# Shield_Cutter-V1.net
KiCad netlist of a schematic drawn in EAGLE
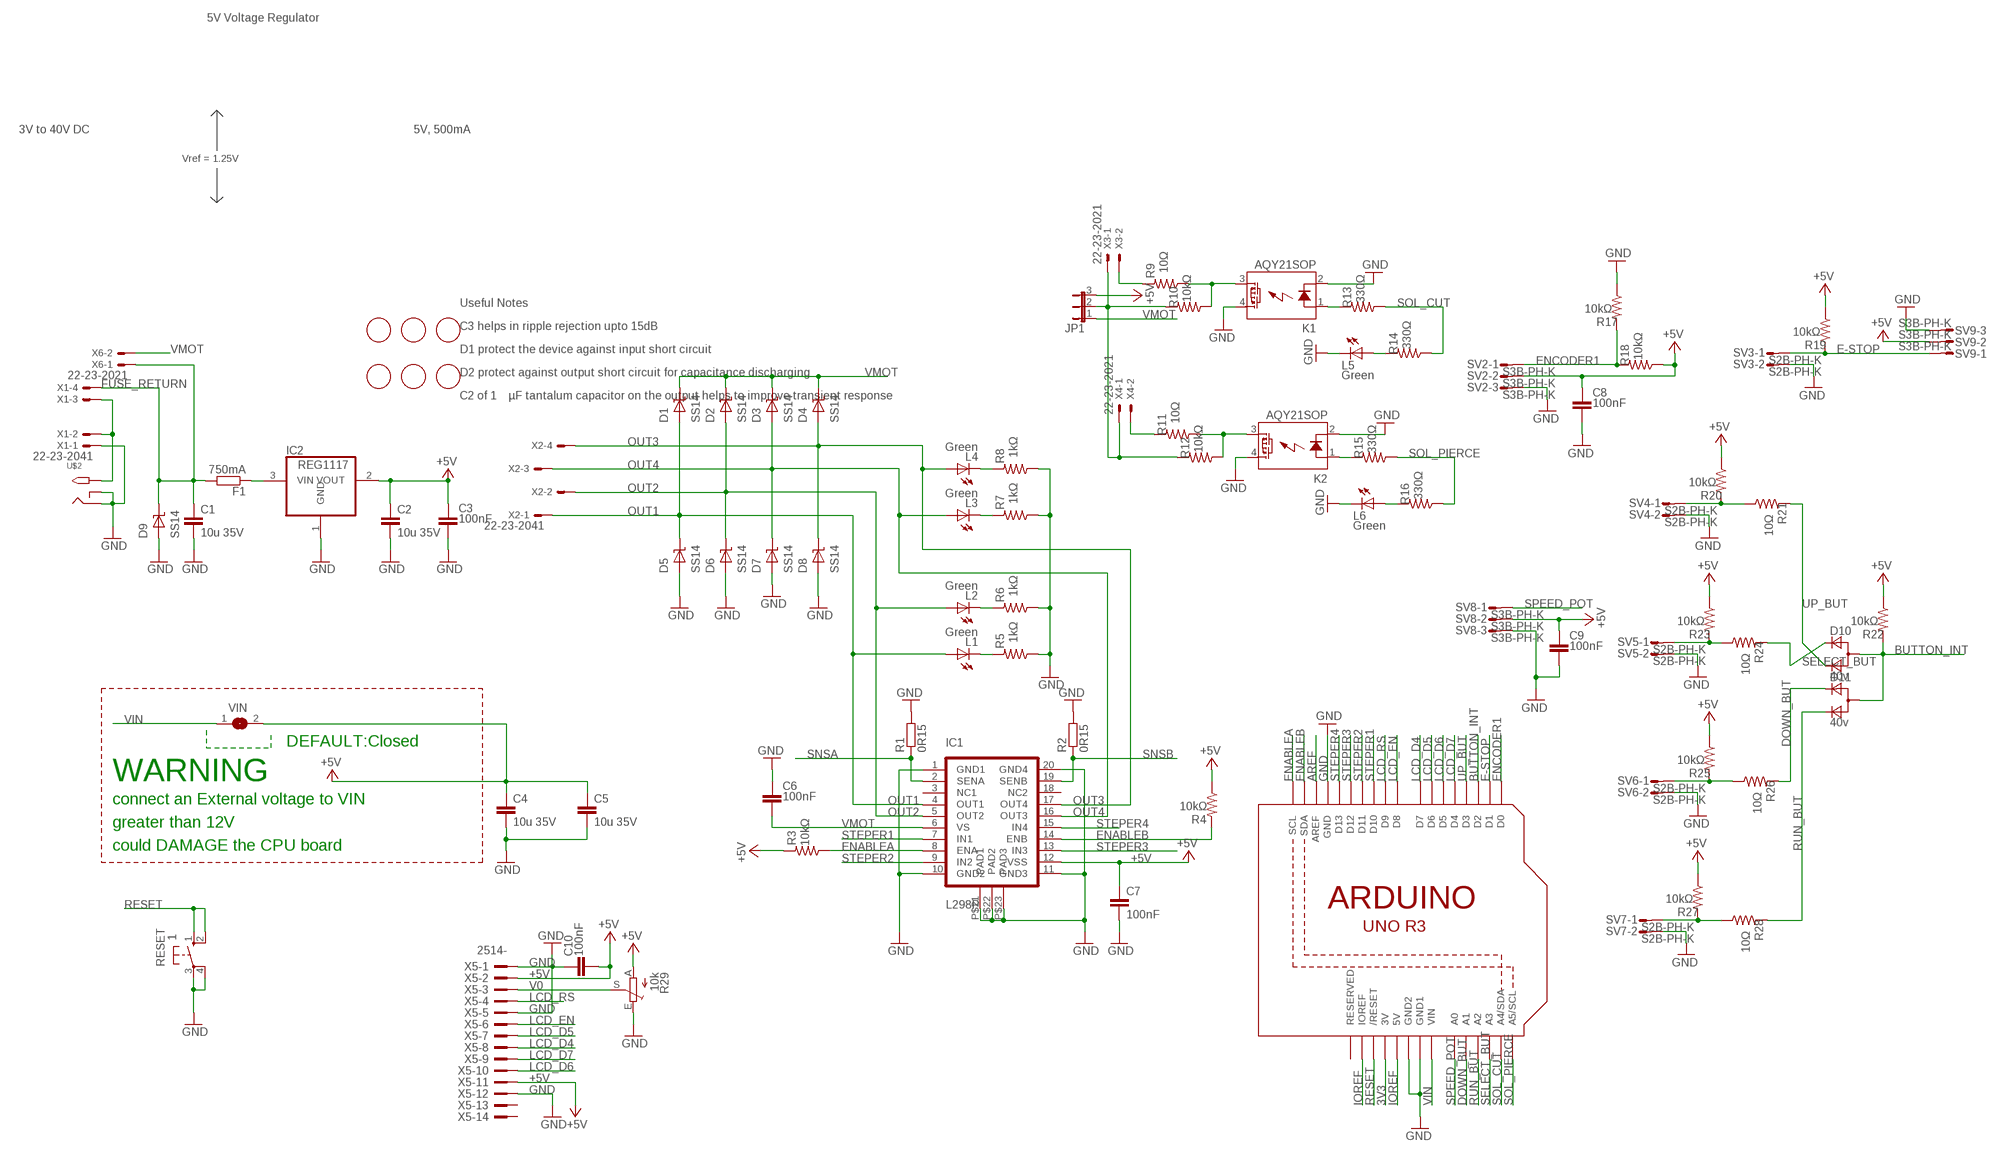
[diagram p0: schematic, sheet 1]

(export (version "E")
  (design (tool "Eeschema 10.0.6"))
  (components
    (comp (ref "C1")
      (value "10u 35V")
      (footprint "eagle-import:C1210")
      (libsource (lib "eagle-import") (part "C-EUC1210"))
    )
    (comp (ref "C2")
      (value "10u 35V")
      (footprint "eagle-import:C1210")
      (libsource (lib "eagle-import") (part "C-EUC1210"))
    )
    (comp (ref "C3")
      (value "100nF")
      (footprint "eagle-import:C0805")
      (libsource (lib "eagle-import") (part "rcl_C-EUC0805"))
    )
    (comp (ref "C4")
      (value "10u 35V")
      (footprint "eagle-import:C1210")
      (libsource (lib "eagle-import") (part "C-EUC1210"))
    )
    (comp (ref "C5")
      (value "10u 35V")
      (footprint "eagle-import:C1210")
      (libsource (lib "eagle-import") (part "C-EUC1210"))
    )
    (comp (ref "C6")
      (value "100nF")
      (footprint "eagle-import:C0805")
      (libsource (lib "eagle-import") (part "rcl_C-EUC0805"))
    )
    (comp (ref "C7")
      (value "100nF")
      (footprint "eagle-import:C0805")
      (libsource (lib "eagle-import") (part "C-EUC0805"))
    )
    (comp (ref "C8")
      (value "100nF")
      (footprint "eagle-import:C0805")
      (libsource (lib "eagle-import") (part "rcl_C-EUC0805"))
    )
    (comp (ref "C9")
      (value "100nF")
      (footprint "eagle-import:C0805")
      (libsource (lib "eagle-import") (part "rcl_C-EUC0805"))
    )
    (comp (ref "C10")
      (value "100nF")
      (footprint "eagle-import:C0805")
      (libsource (lib "eagle-import") (part "rcl_C-EUC0805"))
    )
    (comp (ref "D1")
      (value "SS14")
      (footprint "eagle-import:SMA")
      (libsource (lib "eagle-import") (part "SS14"))
    )
    (comp (ref "D2")
      (value "SS14")
      (footprint "eagle-import:SMA")
      (libsource (lib "eagle-import") (part "SS14"))
    )
    (comp (ref "D3")
      (value "SS14")
      (footprint "eagle-import:SMA")
      (libsource (lib "eagle-import") (part "SS14"))
    )
    (comp (ref "D4")
      (value "SS14")
      (footprint "eagle-import:SMA")
      (libsource (lib "eagle-import") (part "SS14"))
    )
    (comp (ref "D5")
      (value "SS14")
      (footprint "eagle-import:SMA")
      (libsource (lib "eagle-import") (part "SS14"))
    )
    (comp (ref "D6")
      (value "SS14")
      (footprint "eagle-import:SMA")
      (libsource (lib "eagle-import") (part "SS14"))
    )
    (comp (ref "D7")
      (value "SS14")
      (footprint "eagle-import:SMA")
      (libsource (lib "eagle-import") (part "SS14"))
    )
    (comp (ref "D8")
      (value "SS14")
      (footprint "eagle-import:SMA")
      (libsource (lib "eagle-import") (part "SS14"))
    )
    (comp (ref "D9")
      (value "SS14")
      (footprint "eagle-import:SMA")
      (libsource (lib "eagle-import") (part "SS14"))
    )
    (comp (ref "D10")
      (value "40v")
      (footprint "eagle-import:SOT323")
      (libsource (lib "eagle-import") (part "D_2CSOT323"))
    )
    (comp (ref "D11")
      (value "40v")
      (footprint "eagle-import:SOT323")
      (libsource (lib "eagle-import") (part "D_2CSOT323"))
    )
    (comp (ref "F1")
      (value "750mA")
      (footprint "eagle-import:R1206")
      (libsource (lib "eagle-import") (part "R-EU_R1206"))
    )
    (comp (ref "FID1")
      (value "FIDUCIALMOUNT")
      (footprint "eagle-import:FIDUCIA-MOUNT")
      (libsource (lib "eagle-import") (part "FIDUCIALMOUNT"))
    )
    (comp (ref "FID2")
      (value "FIDUCIALMOUNT")
      (footprint "eagle-import:FIDUCIA-MOUNT")
      (libsource (lib "eagle-import") (part "FIDUCIALMOUNT"))
    )
    (comp (ref "FID3")
      (value "FIDUCIALMOUNT")
      (footprint "eagle-import:FIDUCIA-MOUNT")
      (libsource (lib "eagle-import") (part "FIDUCIALMOUNT"))
    )
    (comp (ref "FID4")
      (value "FIDUCIALMOUNT")
      (footprint "eagle-import:FIDUCIA-MOUNT")
      (libsource (lib "eagle-import") (part "FIDUCIALMOUNT"))
    )
    (comp (ref "FID5")
      (value "FIDUCIALMOUNT")
      (footprint "eagle-import:FIDUCIA-MOUNT")
      (libsource (lib "eagle-import") (part "FIDUCIALMOUNT"))
    )
    (comp (ref "FID6")
      (value "FIDUCIALMOUNT")
      (footprint "eagle-import:FIDUCIA-MOUNT")
      (libsource (lib "eagle-import") (part "FIDUCIALMOUNT"))
    )
    (comp (ref "IC1")
      (value "L298P")
      (footprint "eagle-import:POWER-SO20")
      (libsource (lib "eagle-import") (part "L298P"))
    )
    (comp (ref "IC2")
      (value "REG1117")
      (footprint "eagle-import:SOT223")
      (libsource (lib "eagle-import") (part "REG1117"))
    )
    (comp (ref "JP1")
      (value "JP2E")
      (footprint "eagle-import:JP2")
      (libsource (lib "eagle-import") (part "JP2E"))
    )
    (comp (ref "K1")
      (value "AQY21SOP")
      (footprint "eagle-import:SOP04")
      (libsource (lib "eagle-import") (part "AQYSOP21"))
    )
    (comp (ref "K2")
      (value "AQY21SOP")
      (footprint "eagle-import:SOP04")
      (libsource (lib "eagle-import") (part "AQYSOP21"))
    )
    (comp (ref "L1")
      (value "Green")
      (footprint "eagle-import:CHIPLED_0805")
      (libsource (lib "eagle-import") (part "LEDCHIPLED_0805"))
    )
    (comp (ref "L2")
      (value "Green")
      (footprint "eagle-import:CHIPLED_0805")
      (libsource (lib "eagle-import") (part "LEDCHIPLED_0805"))
    )
    (comp (ref "L3")
      (value "Green")
      (footprint "eagle-import:CHIPLED_0805")
      (libsource (lib "eagle-import") (part "LEDCHIPLED_0805"))
    )
    (comp (ref "L4")
      (value "Green")
      (footprint "eagle-import:CHIPLED_0805")
      (libsource (lib "eagle-import") (part "LEDCHIPLED_0805"))
    )
    (comp (ref "L5")
      (value "Green")
      (footprint "eagle-import:CHIPLED_0805")
      (libsource (lib "eagle-import") (part "LEDCHIPLED_0805"))
    )
    (comp (ref "L6")
      (value "Green")
      (footprint "eagle-import:CHIPLED_0805")
      (libsource (lib "eagle-import") (part "LEDCHIPLED_0805"))
    )
    (comp (ref "R1")
      (value "0R15")
      (footprint "eagle-import:R1206")
      (libsource (lib "eagle-import") (part "R-EU_R1206"))
    )
    (comp (ref "R2")
      (value "0R15")
      (footprint "eagle-import:R1206")
      (libsource (lib "eagle-import") (part "R-EU_R1206"))
    )
    (comp (ref "R3")
      (value "10kΩ")
      (footprint "eagle-import:R0805")
      (libsource (lib "eagle-import") (part "R-US_R0805"))
    )
    (comp (ref "R4")
      (value "10kΩ")
      (footprint "eagle-import:R0805")
      (libsource (lib "eagle-import") (part "R-US_R0805"))
    )
    (comp (ref "R5")
      (value "1kΩ")
      (footprint "eagle-import:R0805")
      (libsource (lib "eagle-import") (part "R-US_R0805"))
    )
    (comp (ref "R6")
      (value "1kΩ")
      (footprint "eagle-import:R0805")
      (libsource (lib "eagle-import") (part "R-US_R0805"))
    )
    (comp (ref "R7")
      (value "1kΩ")
      (footprint "eagle-import:R0805")
      (libsource (lib "eagle-import") (part "R-US_R0805"))
    )
    (comp (ref "R8")
      (value "1kΩ")
      (footprint "eagle-import:R0805")
      (libsource (lib "eagle-import") (part "R-US_R0805"))
    )
    (comp (ref "R9")
      (value "10Ω")
      (footprint "eagle-import:R0805")
      (libsource (lib "eagle-import") (part "R-US_R0805"))
    )
    (comp (ref "R10")
      (value "10kΩ")
      (footprint "eagle-import:R0805")
      (libsource (lib "eagle-import") (part "R-US_R0805"))
    )
    (comp (ref "R11")
      (value "10Ω")
      (footprint "eagle-import:R0805")
      (libsource (lib "eagle-import") (part "R-US_R0805"))
    )
    (comp (ref "R12")
      (value "10kΩ")
      (footprint "eagle-import:R0805")
      (libsource (lib "eagle-import") (part "R-US_R0805"))
    )
    (comp (ref "R13")
      (value "330Ω")
      (footprint "eagle-import:R0805")
      (libsource (lib "eagle-import") (part "R-US_R0805"))
    )
    (comp (ref "R14")
      (value "330Ω")
      (footprint "eagle-import:R0805")
      (libsource (lib "eagle-import") (part "R-US_R0805"))
    )
    (comp (ref "R15")
      (value "330Ω")
      (footprint "eagle-import:R0805")
      (libsource (lib "eagle-import") (part "R-US_R0805"))
    )
    (comp (ref "R16")
      (value "330Ω")
      (footprint "eagle-import:R0805")
      (libsource (lib "eagle-import") (part "R-US_R0805"))
    )
    (comp (ref "R17")
      (value "10kΩ")
      (footprint "eagle-import:R0805")
      (libsource (lib "eagle-import") (part "R-US_R0805"))
    )
    (comp (ref "R18")
      (value "10kΩ")
      (footprint "eagle-import:R0805")
      (libsource (lib "eagle-import") (part "R-US_R0805"))
    )
    (comp (ref "R19")
      (value "10kΩ")
      (footprint "eagle-import:R0805")
      (libsource (lib "eagle-import") (part "R-US_R0805"))
    )
    (comp (ref "R20")
      (value "10kΩ")
      (footprint "eagle-import:R0805")
      (libsource (lib "eagle-import") (part "R-US_R0805"))
    )
    (comp (ref "R21")
      (value "10Ω")
      (footprint "eagle-import:R0805")
      (libsource (lib "eagle-import") (part "R-US_R0805"))
    )
    (comp (ref "R22")
      (value "10kΩ")
      (footprint "eagle-import:M0805")
      (libsource (lib "eagle-import") (part "R-US_M0805"))
    )
    (comp (ref "R23")
      (value "10kΩ")
      (footprint "eagle-import:R0805")
      (libsource (lib "eagle-import") (part "R-US_R0805"))
    )
    (comp (ref "R24")
      (value "10Ω")
      (footprint "eagle-import:R0805")
      (libsource (lib "eagle-import") (part "R-US_R0805"))
    )
    (comp (ref "R25")
      (value "10kΩ")
      (footprint "eagle-import:R0805")
      (libsource (lib "eagle-import") (part "R-US_R0805"))
    )
    (comp (ref "R26")
      (value "10Ω")
      (footprint "eagle-import:R0805")
      (libsource (lib "eagle-import") (part "R-US_R0805"))
    )
    (comp (ref "R27")
      (value "10kΩ")
      (footprint "eagle-import:R0805")
      (libsource (lib "eagle-import") (part "R-US_R0805"))
    )
    (comp (ref "R28")
      (value "10Ω")
      (footprint "eagle-import:R0805")
      (libsource (lib "eagle-import") (part "R-US_R0805"))
    )
    (comp (ref "R29")
      (value "10k")
      (footprint "eagle-import:S64W")
      (libsource (lib "eagle-import") (part "TRIM_EU-S64W"))
    )
    (comp (ref "RESET")
      (value "1")
      (footprint "eagle-import:B3F-10XX")
      (fields (field (name "MPN") "B3F-1000"))
      (libsource (lib "eagle-import") (part "10-XX"))
    )
    (comp (ref "SV2")
      (value "S3B-PH-K")
      (footprint "eagle-import:S03P")
      (libsource (lib "eagle-import") (part "S03P"))
    )
    (comp (ref "SV3")
      (value "S2B-PH-K")
      (footprint "eagle-import:S02P")
      (libsource (lib "eagle-import") (part "S02P"))
    )
    (comp (ref "SV4")
      (value "S2B-PH-K")
      (footprint "eagle-import:S02P")
      (libsource (lib "eagle-import") (part "S02P"))
    )
    (comp (ref "SV5")
      (value "S2B-PH-K")
      (footprint "eagle-import:S02P")
      (libsource (lib "eagle-import") (part "S02P"))
    )
    (comp (ref "SV6")
      (value "S2B-PH-K")
      (footprint "eagle-import:S02P")
      (libsource (lib "eagle-import") (part "S02P"))
    )
    (comp (ref "SV7")
      (value "S2B-PH-K")
      (footprint "eagle-import:S02P")
      (libsource (lib "eagle-import") (part "S02P"))
    )
    (comp (ref "SV8")
      (value "S3B-PH-K")
      (footprint "eagle-import:S03P")
      (libsource (lib "eagle-import") (part "S03P"))
    )
    (comp (ref "SV9")
      (value "S3B-PH-K")
      (footprint "eagle-import:S03P")
      (libsource (lib "eagle-import") (part "S03P"))
    )
    (comp (ref "U$2")
      (value "2.1MMJACKTHM")
      (footprint "eagle-import:PJ-102A")
      (libsource (lib "eagle-import") (part "2.1MMJACKTHM"))
    )
    (comp (ref "U1")
      (value "ARDUINOR3-DIMENSION")
      (footprint "eagle-import:ARDUINOR3")
      (libsource (lib "eagle-import") (part "ARDUINOR3-DIMENSION"))
    )
    (comp (ref "VIN")
      (value "SJW")
      (footprint "eagle-import:SJW")
      (libsource (lib "eagle-import") (part "SJW"))
    )
    (comp (ref "X1")
      (value "22-23-2041")
      (footprint "eagle-import:22-23-2041")
      (fields (field (name "MF") "MOLEX"))
      (libsource (lib "eagle-import") (part "22-23-2041"))
    )
    (comp (ref "X2")
      (value "22-23-2041")
      (footprint "eagle-import:22-23-2041")
      (fields (field (name "MF") "MOLEX"))
      (libsource (lib "eagle-import") (part "22-23-2041"))
    )
    (comp (ref "X3")
      (value "22-23-2021")
      (footprint "eagle-import:22-23-2021")
      (fields (field (name "MF") "MOLEX"))
      (libsource (lib "eagle-import") (part "22-23-2021"))
    )
    (comp (ref "X4")
      (value "22-23-2021")
      (footprint "eagle-import:22-23-2021")
      (fields (field (name "MF") "MOLEX"))
      (libsource (lib "eagle-import") (part "22-23-2021"))
    )
    (comp (ref "X5")
      (value "2514-")
      (footprint "eagle-import:PAK100_2500-14")
      (libsource (lib "eagle-import") (part "2514-"))
    )
    (comp (ref "X6")
      (value "22-23-2021")
      (footprint "eagle-import:22-23-2021")
      (fields (field (name "MF") "MOLEX"))
      (libsource (lib "eagle-import") (part "22-23-2021"))
    )
  )
  (nets
    (net (code "1") (name "+5V") (class "Default")
      (node (ref "C10") (pin "2") (pinfunction "2_2") (pintype "passive"))
      (node (ref "C2") (pin "1") (pinfunction "1_1") (pintype "passive"))
      (node (ref "C3") (pin "1") (pinfunction "1_1") (pintype "passive"))
      (node (ref "C4") (pin "1") (pinfunction "1_1") (pintype "passive"))
      (node (ref "C5") (pin "1") (pinfunction "1_1") (pintype "passive"))
      (node (ref "C7") (pin "1") (pinfunction "1_1") (pintype "passive"))
      (node (ref "C8") (pin "1") (pinfunction "1_1") (pintype "passive"))
      (node (ref "C9") (pin "1") (pinfunction "1_1") (pintype "passive"))
      (node (ref "IC1") (pin "P$12") (pinfunction "VSS_P$12") (pintype "power_in"))
      (node (ref "IC2") (pin "2") (pinfunction "VOUT_2") (pintype "output"))
      (node (ref "JP1") (pin "3") (pinfunction "3_3") (pintype "passive"))
      (node (ref "R18") (pin "1") (pinfunction "1_1") (pintype "passive"))
      (node (ref "R19") (pin "1") (pinfunction "1_1") (pintype "passive"))
      (node (ref "R20") (pin "1") (pinfunction "1_1") (pintype "passive"))
      (node (ref "R22") (pin "1") (pinfunction "1_1") (pintype "passive"))
      (node (ref "R23") (pin "1") (pinfunction "1_1") (pintype "passive"))
      (node (ref "R25") (pin "1") (pinfunction "1_1") (pintype "passive"))
      (node (ref "R27") (pin "1") (pinfunction "1_1") (pintype "passive"))
      (node (ref "R29") (pin "A") (pinfunction "A_A") (pintype "passive"))
      (node (ref "R3") (pin "2") (pinfunction "2_2") (pintype "passive"))
      (node (ref "R4") (pin "1") (pinfunction "1_1") (pintype "passive"))
      (node (ref "SV2") (pin "2") (pinfunction "S_2") (pintype "passive"))
      (node (ref "SV8") (pin "2") (pinfunction "S_2") (pintype "passive"))
      (node (ref "SV9") (pin "2") (pinfunction "S_2") (pintype "passive"))
      (node (ref "VIN") (pin "2") (pinfunction "2_2") (pintype "passive"))
      (node (ref "X5") (pin "11") (pinfunction "KL_11") (pintype "passive"))
      (node (ref "X5") (pin "2") (pinfunction "KL_2") (pintype "passive"))
    )
    (net (code "2") (name "/3V3") (class "Default")
      (node (ref "U1") (pin "3V") (pinfunction "3V_3V") (pintype "power_in"))
    )
    (net (code "3") (name "/AREF") (class "Default")
      (node (ref "U1") (pin "AREF") (pinfunction "AREF_AREF") (pintype "bidirectional"))
    )
    (net (code "4") (name "/BUTTON_INT") (class "Default")
      (node (ref "D10") (pin "1") (pinfunction "A_1") (pintype "passive"))
      (node (ref "D11") (pin "1") (pinfunction "A_1") (pintype "passive"))
      (node (ref "R22") (pin "2") (pinfunction "2_2") (pintype "passive"))
      (node (ref "U1") (pin "D2") (pinfunction "D2_D2") (pintype "bidirectional"))
    )
    (net (code "5") (name "/DOWN_BUT") (class "Default")
      (node (ref "D11") (pin "2") (pinfunction "C1_2") (pintype "passive"))
      (node (ref "R26") (pin "2") (pinfunction "2_2") (pintype "passive"))
      (node (ref "U1") (pin "A1") (pinfunction "A1_A1") (pintype "bidirectional"))
    )
    (net (code "6") (name "/E-STOP") (class "Default")
      (node (ref "R19") (pin "2") (pinfunction "2_2") (pintype "passive"))
      (node (ref "SV3") (pin "1") (pinfunction "S_1") (pintype "passive"))
      (node (ref "SV9") (pin "1") (pinfunction "S_1") (pintype "passive"))
      (node (ref "U1") (pin "D1") (pinfunction "D1_D1") (pintype "bidirectional"))
    )
    (net (code "7") (name "/ENABLEA") (class "Default")
      (node (ref "IC1") (pin "P$8") (pinfunction "ENA_P$8") (pintype "input"))
      (node (ref "R3") (pin "1") (pinfunction "1_1") (pintype "passive"))
      (node (ref "U1") (pin "SCL") (pinfunction "SCL_SCL") (pintype "bidirectional"))
    )
    (net (code "8") (name "/ENABLEB") (class "Default")
      (node (ref "IC1") (pin "P$14") (pinfunction "ENB_P$14") (pintype "input"))
      (node (ref "R4") (pin "2") (pinfunction "2_2") (pintype "passive"))
      (node (ref "U1") (pin "SDA") (pinfunction "SDA_SDA") (pintype "bidirectional"))
    )
    (net (code "9") (name "/ENCODER1") (class "Default")
      (node (ref "R17") (pin "2") (pinfunction "2_2") (pintype "passive"))
      (node (ref "R18") (pin "2") (pinfunction "2_2") (pintype "passive"))
      (node (ref "SV2") (pin "1") (pinfunction "S_1") (pintype "passive"))
      (node (ref "U1") (pin "D0") (pinfunction "D0_D0") (pintype "bidirectional"))
    )
    (net (code "10") (name "/FUSE_RETURN") (class "Default")
      (node (ref "C1") (pin "1") (pinfunction "1_1") (pintype "passive"))
      (node (ref "D9") (pin "P$1") (pinfunction "K_P$1") (pintype "bidirectional"))
      (node (ref "F1") (pin "2") (pinfunction "2_2") (pintype "passive"))
      (node (ref "X1") (pin "4") (pinfunction "S_4") (pintype "passive"))
      (node (ref "X6") (pin "1") (pinfunction "S_1") (pintype "passive"))
    )
    (net (code "11") (name "/IOREF") (class "Default")
      (node (ref "U1") (pin "5V") (pinfunction "5V_5V") (pintype "power_in"))
      (node (ref "U1") (pin "IOREF") (pinfunction "IOREF_IOREF") (pintype "output"))
    )
    (net (code "12") (name "/LCD_D4") (class "Default")
      (node (ref "U1") (pin "D7") (pinfunction "D7_D7") (pintype "bidirectional"))
      (node (ref "X5") (pin "8") (pinfunction "KL_8") (pintype "passive"))
    )
    (net (code "13") (name "/LCD_D5") (class "Default")
      (node (ref "U1") (pin "D6") (pinfunction "D6_D6") (pintype "bidirectional"))
      (node (ref "X5") (pin "7") (pinfunction "KL_7") (pintype "passive"))
    )
    (net (code "14") (name "/LCD_D6") (class "Default")
      (node (ref "U1") (pin "D5") (pinfunction "D5_D5") (pintype "bidirectional"))
      (node (ref "X5") (pin "10") (pinfunction "KL_10") (pintype "passive"))
    )
    (net (code "15") (name "/LCD_D7") (class "Default")
      (node (ref "U1") (pin "D4") (pinfunction "D4_D4") (pintype "bidirectional"))
      (node (ref "X5") (pin "9") (pinfunction "KL_9") (pintype "passive"))
    )
    (net (code "16") (name "/LCD_EN") (class "Default")
      (node (ref "U1") (pin "D8") (pinfunction "D8_D8") (pintype "bidirectional"))
      (node (ref "X5") (pin "6") (pinfunction "KL_6") (pintype "passive"))
    )
    (net (code "17") (name "/LCD_RS") (class "Default")
      (node (ref "U1") (pin "D9") (pinfunction "D9_D9") (pintype "bidirectional"))
      (node (ref "X5") (pin "4") (pinfunction "KL_4") (pintype "passive"))
    )
    (net (code "18") (name "/OUT1") (class "Default")
      (node (ref "D1") (pin "P$2") (pinfunction "A_P$2") (pintype "bidirectional"))
      (node (ref "D5") (pin "P$1") (pinfunction "K_P$1") (pintype "bidirectional"))
      (node (ref "IC1") (pin "P$4") (pinfunction "OUT1_P$4") (pintype "output"))
      (node (ref "L1") (pin "A") (pinfunction "A_A") (pintype "passive"))
      (node (ref "X2") (pin "1") (pinfunction "S_1") (pintype "passive"))
    )
    (net (code "19") (name "/OUT2") (class "Default")
      (node (ref "D2") (pin "P$2") (pinfunction "A_P$2") (pintype "bidirectional"))
      (node (ref "D6") (pin "P$1") (pinfunction "K_P$1") (pintype "bidirectional"))
      (node (ref "IC1") (pin "P$5") (pinfunction "OUT2_P$5") (pintype "output"))
      (node (ref "L2") (pin "A") (pinfunction "A_A") (pintype "passive"))
      (node (ref "X2") (pin "2") (pinfunction "S_2") (pintype "passive"))
    )
    (net (code "20") (name "/OUT3") (class "Default")
      (node (ref "D4") (pin "P$2") (pinfunction "A_P$2") (pintype "bidirectional"))
      (node (ref "D8") (pin "P$1") (pinfunction "K_P$1") (pintype "bidirectional"))
      (node (ref "IC1") (pin "P$17") (pinfunction "OUT4_P$17") (pintype "output"))
      (node (ref "L4") (pin "A") (pinfunction "A_A") (pintype "passive"))
      (node (ref "X2") (pin "4") (pinfunction "S_4") (pintype "passive"))
    )
    (net (code "21") (name "/OUT4") (class "Default")
      (node (ref "D3") (pin "P$2") (pinfunction "A_P$2") (pintype "bidirectional"))
      (node (ref "D7") (pin "P$1") (pinfunction "K_P$1") (pintype "bidirectional"))
      (node (ref "IC1") (pin "P$16") (pinfunction "OUT3_P$16") (pintype "output"))
      (node (ref "L3") (pin "A") (pinfunction "A_A") (pintype "passive"))
      (node (ref "X2") (pin "3") (pinfunction "S_3") (pintype "passive"))
    )
    (net (code "22") (name "/RESET") (class "Default")
      (node (ref "RESET") (pin "1") (pinfunction "S_1") (pintype "passive"))
      (node (ref "RESET") (pin "2") (pinfunction "S1_2") (pintype "passive"))
      (node (ref "U1") (pin "RESET") (pinfunction "/RESET_RESET") (pintype "bidirectional"))
    )
    (net (code "23") (name "/RUN_BUT") (class "Default")
      (node (ref "D11") (pin "3") (pinfunction "C2_3") (pintype "passive"))
      (node (ref "R28") (pin "2") (pinfunction "2_2") (pintype "passive"))
      (node (ref "U1") (pin "A2") (pinfunction "A2_A2") (pintype "bidirectional"))
    )
    (net (code "24") (name "/SELECT_BUT") (class "Default")
      (node (ref "D10") (pin "2") (pinfunction "C1_2") (pintype "passive"))
      (node (ref "R24") (pin "2") (pinfunction "2_2") (pintype "passive"))
      (node (ref "U1") (pin "A3") (pinfunction "A3_A3") (pintype "bidirectional"))
    )
    (net (code "25") (name "/SNSA") (class "Default")
      (node (ref "IC1") (pin "P$2") (pinfunction "SENA_P$2") (pintype "input"))
      (node (ref "R1") (pin "1") (pinfunction "1_1") (pintype "passive"))
    )
    (net (code "26") (name "/SNSB") (class "Default")
      (node (ref "IC1") (pin "P$19") (pinfunction "SENB_P$19") (pintype "input"))
      (node (ref "R2") (pin "1") (pinfunction "1_1") (pintype "passive"))
    )
    (net (code "27") (name "/SOL_CUT") (class "Default")
      (node (ref "R13") (pin "1") (pinfunction "1_1") (pintype "passive"))
      (node (ref "R14") (pin "1") (pinfunction "1_1") (pintype "passive"))
      (node (ref "U1") (pin "A4") (pinfunction "A4/SDA_A4") (pintype "bidirectional"))
    )
    (net (code "28") (name "/SOL_PIERCE") (class "Default")
      (node (ref "R15") (pin "1") (pinfunction "1_1") (pintype "passive"))
      (node (ref "R16") (pin "1") (pinfunction "1_1") (pintype "passive"))
      (node (ref "U1") (pin "A5") (pinfunction "A5/SCL_A5") (pintype "bidirectional"))
    )
    (net (code "29") (name "/SPEED_POT") (class "Default")
      (node (ref "SV8") (pin "1") (pinfunction "S_1") (pintype "passive"))
      (node (ref "U1") (pin "A0") (pinfunction "A0_A0") (pintype "bidirectional"))
    )
    (net (code "30") (name "/STEPER1") (class "Default")
      (node (ref "IC1") (pin "P$7") (pinfunction "IN1_P$7") (pintype "input"))
      (node (ref "U1") (pin "D10") (pinfunction "D10_D10") (pintype "bidirectional"))
    )
    (net (code "31") (name "/STEPER2") (class "Default")
      (node (ref "IC1") (pin "P$9") (pinfunction "IN2_P$9") (pintype "input"))
      (node (ref "U1") (pin "D11") (pinfunction "D11_D11") (pintype "bidirectional"))
    )
    (net (code "32") (name "/STEPER3") (class "Default")
      (node (ref "IC1") (pin "P$13") (pinfunction "IN3_P$13") (pintype "input"))
      (node (ref "U1") (pin "D12") (pinfunction "D12_D12") (pintype "bidirectional"))
    )
    (net (code "33") (name "/STEPER4") (class "Default")
      (node (ref "IC1") (pin "P$15") (pinfunction "IN4_P$15") (pintype "input"))
      (node (ref "U1") (pin "D13") (pinfunction "D13_D13") (pintype "bidirectional"))
    )
    (net (code "34") (name "/UP_BUT") (class "Default")
      (node (ref "D10") (pin "3") (pinfunction "C2_3") (pintype "passive"))
      (node (ref "R21") (pin "2") (pinfunction "2_2") (pintype "passive"))
      (node (ref "U1") (pin "D3") (pinfunction "D3_D3") (pintype "bidirectional"))
    )
    (net (code "35") (name "/V0") (class "Default")
      (node (ref "R29") (pin "S") (pinfunction "S_S") (pintype "passive"))
      (node (ref "X5") (pin "3") (pinfunction "KL_3") (pintype "passive"))
    )
    (net (code "36") (name "/VIN") (class "Default")
      (node (ref "U1") (pin "VIN") (pinfunction "VIN_VIN") (pintype "power_in"))
      (node (ref "VIN") (pin "1") (pinfunction "1_1") (pintype "passive"))
    )
    (net (code "37") (name "/VMOT") (class "Default")
      (node (ref "C6") (pin "2") (pinfunction "2_2") (pintype "passive"))
      (node (ref "D1") (pin "P$1") (pinfunction "K_P$1") (pintype "bidirectional"))
      (node (ref "D2") (pin "P$1") (pinfunction "K_P$1") (pintype "bidirectional"))
      (node (ref "D3") (pin "P$1") (pinfunction "K_P$1") (pintype "bidirectional"))
      (node (ref "D4") (pin "P$1") (pinfunction "K_P$1") (pintype "bidirectional"))
      (node (ref "IC1") (pin "P$6") (pinfunction "VS_P$6") (pintype "power_in"))
      (node (ref "JP1") (pin "1") (pinfunction "1_1") (pintype "passive"))
      (node (ref "X6") (pin "2") (pinfunction "S_2") (pintype "passive"))
    )
    (net (code "38") (name "GND") (class "Default")
      (node (ref "C1") (pin "2") (pinfunction "2_2") (pintype "passive"))
      (node (ref "C10") (pin "1") (pinfunction "1_1") (pintype "passive"))
      (node (ref "C2") (pin "2") (pinfunction "2_2") (pintype "passive"))
      (node (ref "C3") (pin "2") (pinfunction "2_2") (pintype "passive"))
      (node (ref "C4") (pin "2") (pinfunction "2_2") (pintype "passive"))
      (node (ref "C5") (pin "2") (pinfunction "2_2") (pintype "passive"))
      (node (ref "C6") (pin "1") (pinfunction "1_1") (pintype "passive"))
      (node (ref "C7") (pin "2") (pinfunction "2_2") (pintype "passive"))
      (node (ref "C8") (pin "2") (pinfunction "2_2") (pintype "passive"))
      (node (ref "C9") (pin "2") (pinfunction "2_2") (pintype "passive"))
      (node (ref "D5") (pin "P$2") (pinfunction "A_P$2") (pintype "bidirectional"))
      (node (ref "D6") (pin "P$2") (pinfunction "A_P$2") (pintype "bidirectional"))
      (node (ref "D7") (pin "P$2") (pinfunction "A_P$2") (pintype "bidirectional"))
      (node (ref "D8") (pin "P$2") (pinfunction "A_P$2") (pintype "bidirectional"))
      (node (ref "D9") (pin "P$2") (pinfunction "A_P$2") (pintype "bidirectional"))
      (node (ref "IC1") (pin "P$1") (pinfunction "GND1_P$1") (pintype "power_in"))
      (node (ref "IC1") (pin "P$10") (pinfunction "GND2_P$10") (pintype "power_in"))
      (node (ref "IC1") (pin "P$11") (pinfunction "GND3_P$11") (pintype "power_in"))
      (node (ref "IC1") (pin "P$20") (pinfunction "GND4_P$20") (pintype "power_in"))
      (node (ref "IC1") (pin "P$21") (pinfunction "PAD1_P$21") (pintype "passive"))
      (node (ref "IC1") (pin "P$22") (pinfunction "PAD2_P$22") (pintype "passive"))
      (node (ref "IC1") (pin "P$23") (pinfunction "PAD3_P$23") (pintype "passive"))
      (node (ref "IC2") (pin "1") (pinfunction "GND_1") (pintype "power_in"))
      (node (ref "K1") (pin "2") (pinfunction "K_2") (pintype "passive"))
      (node (ref "K1") (pin "4") (pinfunction "DS1_4") (pintype "passive"))
      (node (ref "K2") (pin "2") (pinfunction "K_2") (pintype "passive"))
      (node (ref "K2") (pin "4") (pinfunction "DS1_4") (pintype "passive"))
      (node (ref "L5") (pin "C") (pinfunction "C_C") (pintype "passive"))
      (node (ref "L6") (pin "C") (pinfunction "C_C") (pintype "passive"))
      (node (ref "R1") (pin "2") (pinfunction "2_2") (pintype "passive"))
      (node (ref "R17") (pin "1") (pinfunction "1_1") (pintype "passive"))
      (node (ref "R2") (pin "2") (pinfunction "2_2") (pintype "passive"))
      (node (ref "R29") (pin "E") (pinfunction "E_E") (pintype "passive"))
      (node (ref "R5") (pin "1") (pinfunction "1_1") (pintype "passive"))
      (node (ref "R6") (pin "1") (pinfunction "1_1") (pintype "passive"))
      (node (ref "R7") (pin "1") (pinfunction "1_1") (pintype "passive"))
      (node (ref "R8") (pin "1") (pinfunction "1_1") (pintype "passive"))
      (node (ref "RESET") (pin "3") (pinfunction "P_3") (pintype "passive"))
      (node (ref "RESET") (pin "4") (pinfunction "P1_4") (pintype "passive"))
      (node (ref "SV2") (pin "3") (pinfunction "S_3") (pintype "passive"))
      (node (ref "SV3") (pin "2") (pinfunction "S_2") (pintype "passive"))
      (node (ref "SV4") (pin "2") (pinfunction "S_2") (pintype "passive"))
      (node (ref "SV5") (pin "2") (pinfunction "S_2") (pintype "passive"))
      (node (ref "SV6") (pin "2") (pinfunction "S_2") (pintype "passive"))
      (node (ref "SV7") (pin "2") (pinfunction "S_2") (pintype "passive"))
      (node (ref "SV8") (pin "3") (pinfunction "S_3") (pintype "passive"))
      (node (ref "SV9") (pin "3") (pinfunction "S_3") (pintype "passive"))
      (node (ref "U$2") (pin "RING") (pinfunction "RING_RING") (pintype "bidirectional"))
      (node (ref "U$2") (pin "RING_SW") (pinfunction "RING_SW_RING_SW") (pintype "bidirectional"))
      (node (ref "U1") (pin "GND") (pinfunction "GND_GND") (pintype "power_in"))
      (node (ref "U1") (pin "GND1") (pinfunction "GND1_GND1") (pintype "power_in"))
      (node (ref "U1") (pin "GND2") (pinfunction "GND2_GND2") (pintype "power_in"))
      (node (ref "X1") (pin "1") (pinfunction "S_1") (pintype "passive"))
      (node (ref "X5") (pin "1") (pinfunction "KL_1") (pintype "passive"))
      (node (ref "X5") (pin "12") (pinfunction "KL_12") (pintype "passive"))
      (node (ref "X5") (pin "5") (pinfunction "KL_5") (pintype "passive"))
    )
    (net (code "39") (name "Net-(IC2-VIN)") (class "Default")
      (node (ref "F1") (pin "1") (pinfunction "1_1") (pintype "passive"))
      (node (ref "IC2") (pin "3") (pinfunction "VIN_3") (pintype "input"))
    )
    (net (code "40") (name "Net-(K1-A)") (class "Default")
      (node (ref "K1") (pin "1") (pinfunction "A_1") (pintype "passive"))
      (node (ref "R13") (pin "2") (pinfunction "2_2") (pintype "passive"))
    )
    (net (code "41") (name "Net-(K1-DS2)") (class "Default")
      (node (ref "K1") (pin "3") (pinfunction "DS2_3") (pintype "passive"))
      (node (ref "R10") (pin "1") (pinfunction "1_1") (pintype "passive"))
      (node (ref "R9") (pin "1") (pinfunction "1_1") (pintype "passive"))
    )
    (net (code "42") (name "Net-(K2-A)") (class "Default")
      (node (ref "K2") (pin "1") (pinfunction "A_1") (pintype "passive"))
      (node (ref "R15") (pin "2") (pinfunction "2_2") (pintype "passive"))
    )
    (net (code "43") (name "Net-(K2-DS2)") (class "Default")
      (node (ref "K2") (pin "3") (pinfunction "DS2_3") (pintype "passive"))
      (node (ref "R11") (pin "1") (pinfunction "1_1") (pintype "passive"))
      (node (ref "R12") (pin "1") (pinfunction "1_1") (pintype "passive"))
    )
    (net (code "44") (name "Net-(L1-PadC)") (class "Default")
      (node (ref "L1") (pin "C") (pinfunction "C_C") (pintype "passive"))
      (node (ref "R5") (pin "2") (pinfunction "2_2") (pintype "passive"))
    )
    (net (code "45") (name "Net-(L2-PadC)") (class "Default")
      (node (ref "L2") (pin "C") (pinfunction "C_C") (pintype "passive"))
      (node (ref "R6") (pin "2") (pinfunction "2_2") (pintype "passive"))
    )
    (net (code "46") (name "Net-(L3-PadC)") (class "Default")
      (node (ref "L3") (pin "C") (pinfunction "C_C") (pintype "passive"))
      (node (ref "R7") (pin "2") (pinfunction "2_2") (pintype "passive"))
    )
    (net (code "47") (name "Net-(L4-PadC)") (class "Default")
      (node (ref "L4") (pin "C") (pinfunction "C_C") (pintype "passive"))
      (node (ref "R8") (pin "2") (pinfunction "2_2") (pintype "passive"))
    )
    (net (code "48") (name "Net-(L5-PadA)") (class "Default")
      (node (ref "L5") (pin "A") (pinfunction "A_A") (pintype "passive"))
      (node (ref "R14") (pin "2") (pinfunction "2_2") (pintype "passive"))
    )
    (net (code "49") (name "Net-(L6-PadA)") (class "Default")
      (node (ref "L6") (pin "A") (pinfunction "A_A") (pintype "passive"))
      (node (ref "R16") (pin "2") (pinfunction "2_2") (pintype "passive"))
    )
    (net (code "50") (name "Net-(SV4A-S)") (class "Default")
      (node (ref "R20") (pin "2") (pinfunction "2_2") (pintype "passive"))
      (node (ref "R21") (pin "1") (pinfunction "1_1") (pintype "passive"))
      (node (ref "SV4") (pin "1") (pinfunction "S_1") (pintype "passive"))
    )
    (net (code "51") (name "Net-(SV5A-S)") (class "Default")
      (node (ref "R23") (pin "2") (pinfunction "2_2") (pintype "passive"))
      (node (ref "R24") (pin "1") (pinfunction "1_1") (pintype "passive"))
      (node (ref "SV5") (pin "1") (pinfunction "S_1") (pintype "passive"))
    )
    (net (code "52") (name "Net-(SV6A-S)") (class "Default")
      (node (ref "R25") (pin "2") (pinfunction "2_2") (pintype "passive"))
      (node (ref "R26") (pin "1") (pinfunction "1_1") (pintype "passive"))
      (node (ref "SV6") (pin "1") (pinfunction "S_1") (pintype "passive"))
    )
    (net (code "53") (name "Net-(SV7A-S)") (class "Default")
      (node (ref "R27") (pin "2") (pinfunction "2_2") (pintype "passive"))
      (node (ref "R28") (pin "1") (pinfunction "1_1") (pintype "passive"))
      (node (ref "SV7") (pin "1") (pinfunction "S_1") (pintype "passive"))
    )
    (net (code "54") (name "Net-(X1B-S)") (class "Default")
      (node (ref "U$2") (pin "TIP") (pinfunction "TIP_TIP") (pintype "bidirectional"))
      (node (ref "X1") (pin "2") (pinfunction "S_2") (pintype "passive"))
      (node (ref "X1") (pin "3") (pinfunction "S_3") (pintype "passive"))
    )
    (net (code "55") (name "Net-(X3A-S)") (class "Default")
      (node (ref "JP1") (pin "2") (pinfunction "2_2") (pintype "passive"))
      (node (ref "R10") (pin "2") (pinfunction "2_2") (pintype "passive"))
      (node (ref "R12") (pin "2") (pinfunction "2_2") (pintype "passive"))
      (node (ref "X3") (pin "1") (pinfunction "S_1") (pintype "passive"))
      (node (ref "X4") (pin "1") (pinfunction "S_1") (pintype "passive"))
    )
    (net (code "56") (name "Net-(X3B-S)") (class "Default")
      (node (ref "R9") (pin "2") (pinfunction "2_2") (pintype "passive"))
      (node (ref "X3") (pin "2") (pinfunction "S_2") (pintype "passive"))
    )
    (net (code "57") (name "Net-(X4B-S)") (class "Default")
      (node (ref "R11") (pin "2") (pinfunction "2_2") (pintype "passive"))
      (node (ref "X4") (pin "2") (pinfunction "S_2") (pintype "passive"))
    )
    (net (code "58") (name "unconnected-(IC1-NC1-PadP$3)") (class "Default")
      (node (ref "IC1") (pin "P$3") (pinfunction "NC1_P$3") (pintype "no_connect"))
    )
    (net (code "59") (name "unconnected-(IC1-NC2-PadP$18)") (class "Default")
      (node (ref "IC1") (pin "P$18") (pinfunction "NC2_P$18") (pintype "no_connect"))
    )
    (net (code "60") (name "unconnected-(U1-PadRESERVED)") (class "Default")
      (node (ref "U1") (pin "RESERVED") (pinfunction "RESERVED_RESERVED") (pintype "no_connect"))
    )
    (net (code "61") (name "unconnected-(X5E-KL-Pad13)") (class "Default")
      (node (ref "X5") (pin "13") (pinfunction "KL_13") (pintype "passive"))
    )
    (net (code "62") (name "unconnected-(X5F-KL-Pad14)") (class "Default")
      (node (ref "X5") (pin "14") (pinfunction "KL_14") (pintype "passive"))
    )
  )
)
